# SOFTWEAR_microbit.net
KiCad netlist of a schematic drawn in EAGLE
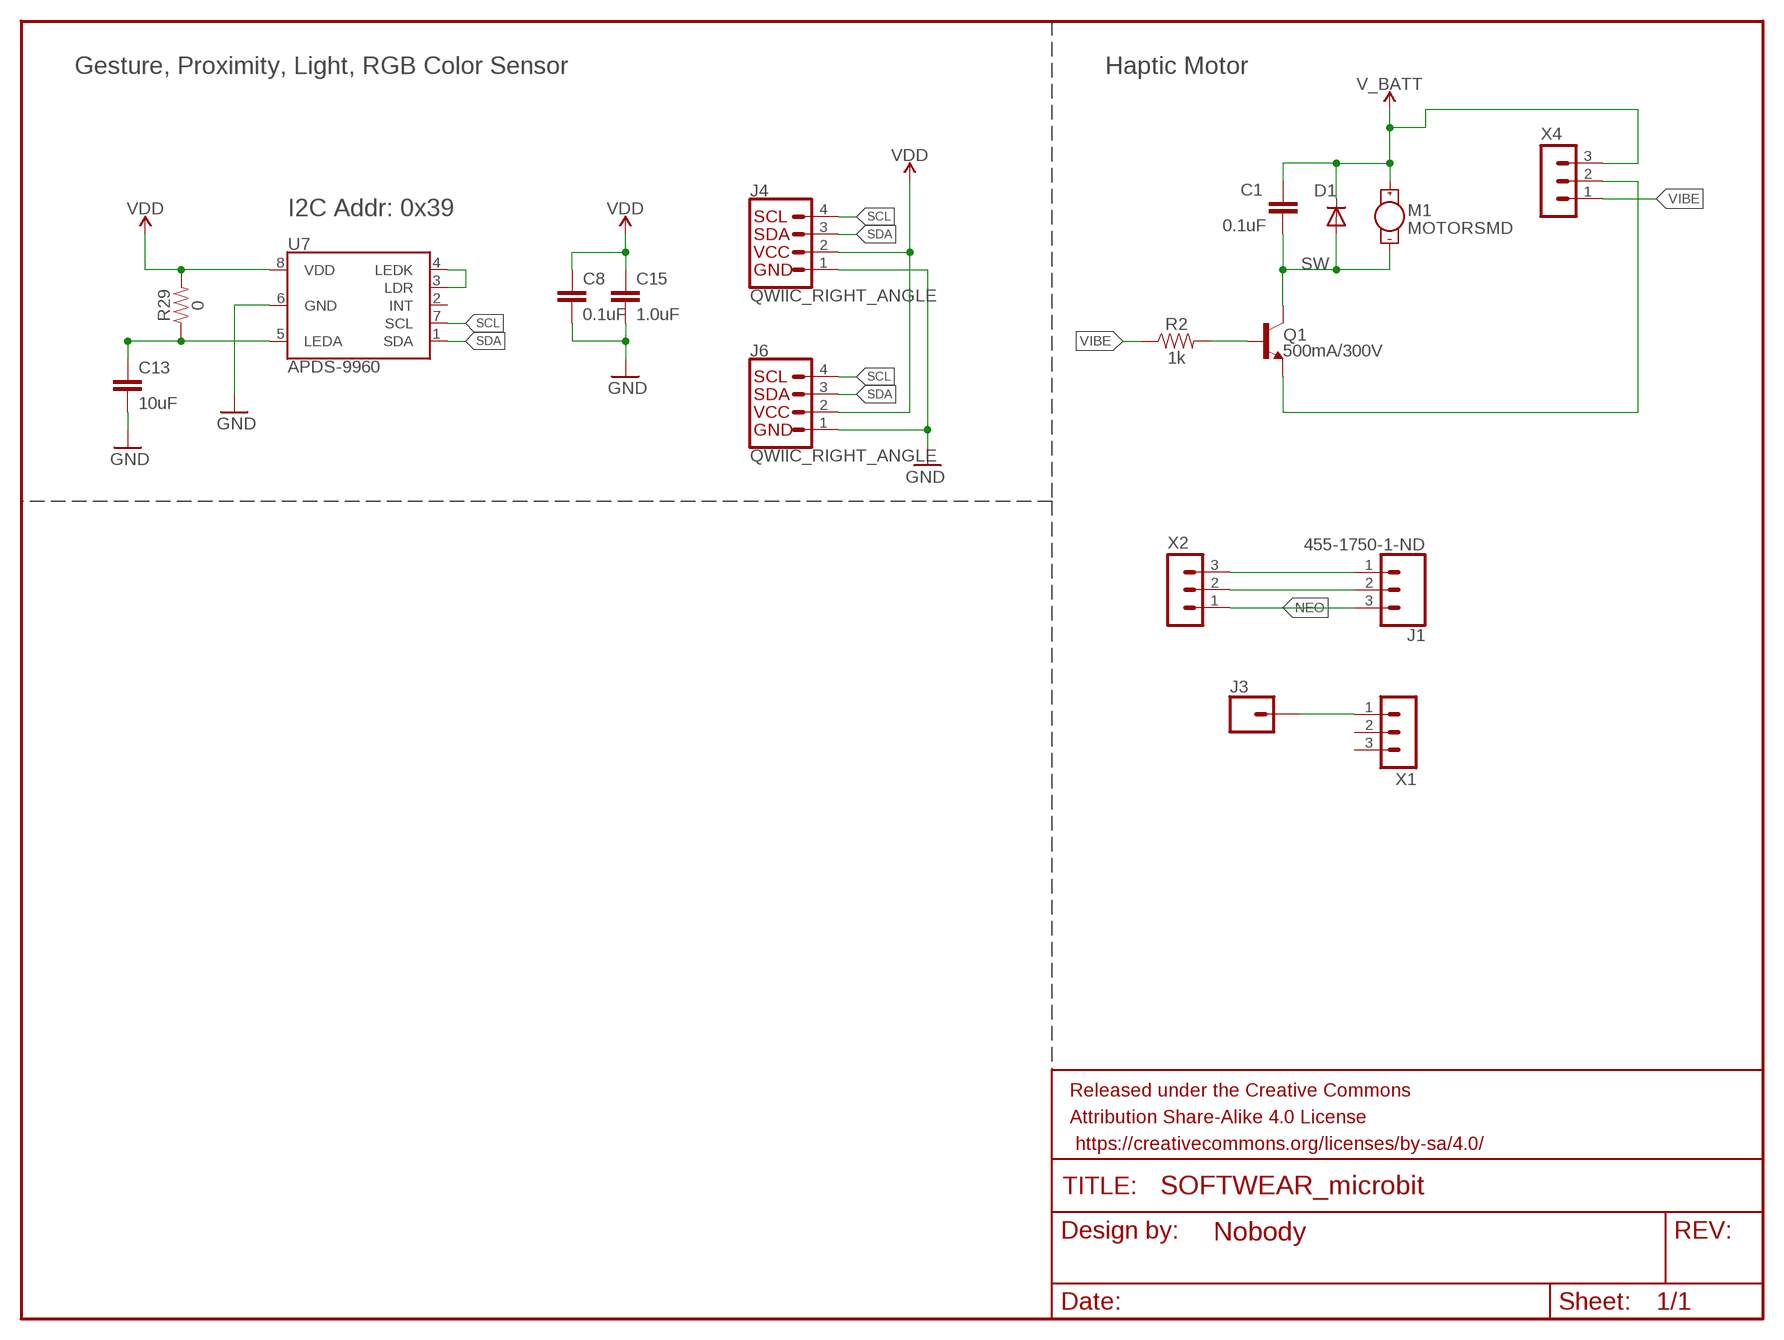
[diagram p0: schematic, sheet 1]

(export (version "E")
  (design (tool "Eeschema 10.0.6"))
  (components
    (comp (ref "C1")
      (value "0.1uF")
      (footprint "eagle-import:0603")
      (libsource (lib "eagle-import") (part "0.1UF-0603-25V-(+80/-20%)"))
    )
    (comp (ref "C8")
      (value "0.1uF")
      (footprint "eagle-import:0603")
      (libsource (lib "eagle-import") (part "0.1UF-0603-25V-(+80/-20%)"))
    )
    (comp (ref "C13")
      (value "10uF")
      (footprint "eagle-import:0805")
      (libsource (lib "eagle-import") (part "10UF-0805-10V-10%"))
    )
    (comp (ref "C15")
      (value "1.0uF")
      (footprint "eagle-import:0603")
      (libsource (lib "eagle-import") (part "1.0UF-0603-16V-10%"))
    )
    (comp (ref "D1")
      (value "DIODESOD")
      (footprint "eagle-import:SOD-323")
      (libsource (lib "eagle-import") (part "DIODESOD"))
    )
    (comp (ref "FRAME2")
      (value "FRAME-LETTERNO_PACKAGE")
      (footprint "eagle-import:DUMMY")
      (fields (field (name "DESIGNER") "Nobody"))
      (libsource (lib "eagle-import") (part "FRAME-LETTERNO_PACKAGE"))
    )
    (comp (ref "J1")
      (value "455-1750-1-ND")
      (footprint "eagle-import:1X03")
      (libsource (lib "eagle-import") (part "CONN_03"))
    )
    (comp (ref "J3")
      (value "CONN_01SPRING-CONN")
      (footprint "eagle-import:SPRING-CONNECTOR")
      (libsource (lib "eagle-import") (part "CONN_01SPRING-CONN"))
    )
    (comp (ref "J4")
      (value "QWIIC_RIGHT_ANGLE")
      (footprint "eagle-import:JST04_1MM_RA")
      (libsource (lib "eagle-import") (part "QWIIC_CONNECTORJS-1MM"))
    )
    (comp (ref "J6")
      (value "QWIIC_RIGHT_ANGLE")
      (footprint "eagle-import:JST04_1MM_RA")
      (libsource (lib "eagle-import") (part "QWIIC_CONNECTORJS-1MM"))
    )
    (comp (ref "M1")
      (value "MOTORSMD")
      (footprint "eagle-import:VIBE-MOTOR-10MM-SMD")
      (libsource (lib "eagle-import") (part "MOTORSMD"))
    )
    (comp (ref "Q1")
      (value "500mA/300V")
      (footprint "eagle-import:SOT23-3")
      (libsource (lib "eagle-import") (part "TRANS_NPN-MMBTA42"))
    )
    (comp (ref "R2")
      (value "1k")
      (footprint "eagle-import:0603")
      (libsource (lib "eagle-import") (part "1KOHM-0603-1/10W-1%"))
    )
    (comp (ref "R29")
      (value "0")
      (footprint "eagle-import:0603")
      (libsource (lib "eagle-import") (part "0OHM-0603-1/10W-5%"))
    )
    (comp (ref "U7")
      (value "APDS-9960")
      (footprint "eagle-import:APDS-9960")
      (libsource (lib "eagle-import") (part "APDS-9960"))
    )
    (comp (ref "X1")
      (value "SM03B-SRSS-TB")
      (footprint "eagle-import:SM03B-SRSS-TB")
      (libsource (lib "eagle-import") (part "SM03B-SRSS-TB"))
    )
    (comp (ref "X2")
      (value "SM03B-SRSS-TB")
      (footprint "eagle-import:SM03B-SRSS-TB")
      (libsource (lib "eagle-import") (part "SM03B-SRSS-TB"))
    )
    (comp (ref "X4")
      (value "SM03B-SRSS-TB")
      (footprint "eagle-import:SM03B-SRSS-TB")
      (libsource (lib "eagle-import") (part "SM03B-SRSS-TB"))
    )
  )
  (nets
    (net (code "1") (name "/SW") (class "Default")
      (node (ref "C1") (pin "2") (pinfunction "2_2") (pintype "passive"))
      (node (ref "D1") (pin "2") (pinfunction "A_2") (pintype "passive"))
      (node (ref "M1") (pin "P$2") (pinfunction "-_P$2") (pintype "bidirectional"))
      (node (ref "Q1") (pin "3") (pinfunction "C_3") (pintype "passive"))
    )
    (net (code "2") (name "GND") (class "Default")
      (node (ref "C13") (pin "2") (pinfunction "2_2") (pintype "passive"))
      (node (ref "C15") (pin "2") (pinfunction "2_2") (pintype "passive"))
      (node (ref "C8") (pin "2") (pinfunction "2_2") (pintype "passive"))
      (node (ref "J4") (pin "1") (pinfunction "1_1") (pintype "power_in"))
      (node (ref "J6") (pin "1") (pinfunction "1_1") (pintype "power_in"))
      (node (ref "U7") (pin "6") (pinfunction "GND_6") (pintype "bidirectional"))
    )
    (net (code "3") (name "NEO") (class "Default")
      (node (ref "J1") (pin "3") (pinfunction "3_3") (pintype "passive"))
      (node (ref "X2") (pin "1") (pinfunction "1_1") (pintype "passive"))
    )
    (net (code "4") (name "Net-(J1-Pad1)") (class "Default")
      (node (ref "J1") (pin "1") (pinfunction "1_1") (pintype "passive"))
      (node (ref "X2") (pin "3") (pinfunction "3_3") (pintype "passive"))
    )
    (net (code "5") (name "Net-(J1-Pad2)") (class "Default")
      (node (ref "J1") (pin "2") (pinfunction "2_2") (pintype "passive"))
      (node (ref "X2") (pin "2") (pinfunction "2_2") (pintype "passive"))
    )
    (net (code "6") (name "Net-(J3-1)") (class "Default")
      (node (ref "J3") (pin "P$2") (pinfunction "1_P$2") (pintype "passive"))
      (node (ref "X1") (pin "1") (pinfunction "1_1") (pintype "passive"))
    )
    (net (code "7") (name "Net-(Q1-B)") (class "Default")
      (node (ref "Q1") (pin "1") (pinfunction "B_1") (pintype "passive"))
      (node (ref "R2") (pin "2") (pinfunction "2_2") (pintype "passive"))
    )
    (net (code "8") (name "Net-(Q1-E)") (class "Default")
      (node (ref "Q1") (pin "2") (pinfunction "E_2") (pintype "passive"))
      (node (ref "X4") (pin "2") (pinfunction "2_2") (pintype "passive"))
    )
    (net (code "9") (name "Net-(U7-LDR)") (class "Default")
      (node (ref "U7") (pin "3") (pinfunction "LDR_3") (pintype "bidirectional"))
      (node (ref "U7") (pin "4") (pinfunction "LEDK_4") (pintype "bidirectional"))
    )
    (net (code "10") (name "Net-(U7-LEDA)") (class "Default")
      (node (ref "C13") (pin "1") (pinfunction "1_1") (pintype "passive"))
      (node (ref "R29") (pin "1") (pinfunction "1_1") (pintype "passive"))
      (node (ref "U7") (pin "5") (pinfunction "LEDA_5") (pintype "bidirectional"))
    )
    (net (code "11") (name "SCL") (class "Default")
      (node (ref "J4") (pin "4") (pinfunction "4_4") (pintype "passive"))
      (node (ref "J6") (pin "4") (pinfunction "4_4") (pintype "passive"))
      (node (ref "U7") (pin "7") (pinfunction "SCL_7") (pintype "bidirectional"))
    )
    (net (code "12") (name "SDA") (class "Default")
      (node (ref "J4") (pin "3") (pinfunction "3_3") (pintype "passive"))
      (node (ref "J6") (pin "3") (pinfunction "3_3") (pintype "passive"))
      (node (ref "U7") (pin "1") (pinfunction "SDA_1") (pintype "bidirectional"))
    )
    (net (code "13") (name "VDD") (class "Default")
      (node (ref "C15") (pin "1") (pinfunction "1_1") (pintype "passive"))
      (node (ref "C8") (pin "1") (pinfunction "1_1") (pintype "passive"))
      (node (ref "J4") (pin "2") (pinfunction "2_2") (pintype "power_in"))
      (node (ref "J6") (pin "2") (pinfunction "2_2") (pintype "power_in"))
      (node (ref "R29") (pin "2") (pinfunction "2_2") (pintype "passive"))
      (node (ref "U7") (pin "8") (pinfunction "VDD_8") (pintype "bidirectional"))
    )
    (net (code "14") (name "VIBE") (class "Default")
      (node (ref "R2") (pin "1") (pinfunction "1_1") (pintype "passive"))
      (node (ref "X4") (pin "1") (pinfunction "1_1") (pintype "passive"))
    )
    (net (code "15") (name "V_BATT") (class "Default")
      (node (ref "C1") (pin "1") (pinfunction "1_1") (pintype "passive"))
      (node (ref "D1") (pin "1") (pinfunction "C_1") (pintype "passive"))
      (node (ref "M1") (pin "P$1") (pinfunction "+_P$1") (pintype "bidirectional"))
      (node (ref "X4") (pin "3") (pinfunction "3_3") (pintype "passive"))
    )
    (net (code "16") (name "unconnected-(U7-INT-Pad2)") (class "Default")
      (node (ref "U7") (pin "2") (pinfunction "INT_2") (pintype "bidirectional"))
    )
    (net (code "17") (name "unconnected-(X1-Pad2)") (class "Default")
      (node (ref "X1") (pin "2") (pinfunction "2_2") (pintype "passive"))
    )
    (net (code "18") (name "unconnected-(X1-Pad3)") (class "Default")
      (node (ref "X1") (pin "3") (pinfunction "3_3") (pintype "passive"))
    )
  )
)
